# Adafruit_NeoPixel_Ring_16.net
KiCad netlist of a schematic drawn in EAGLE
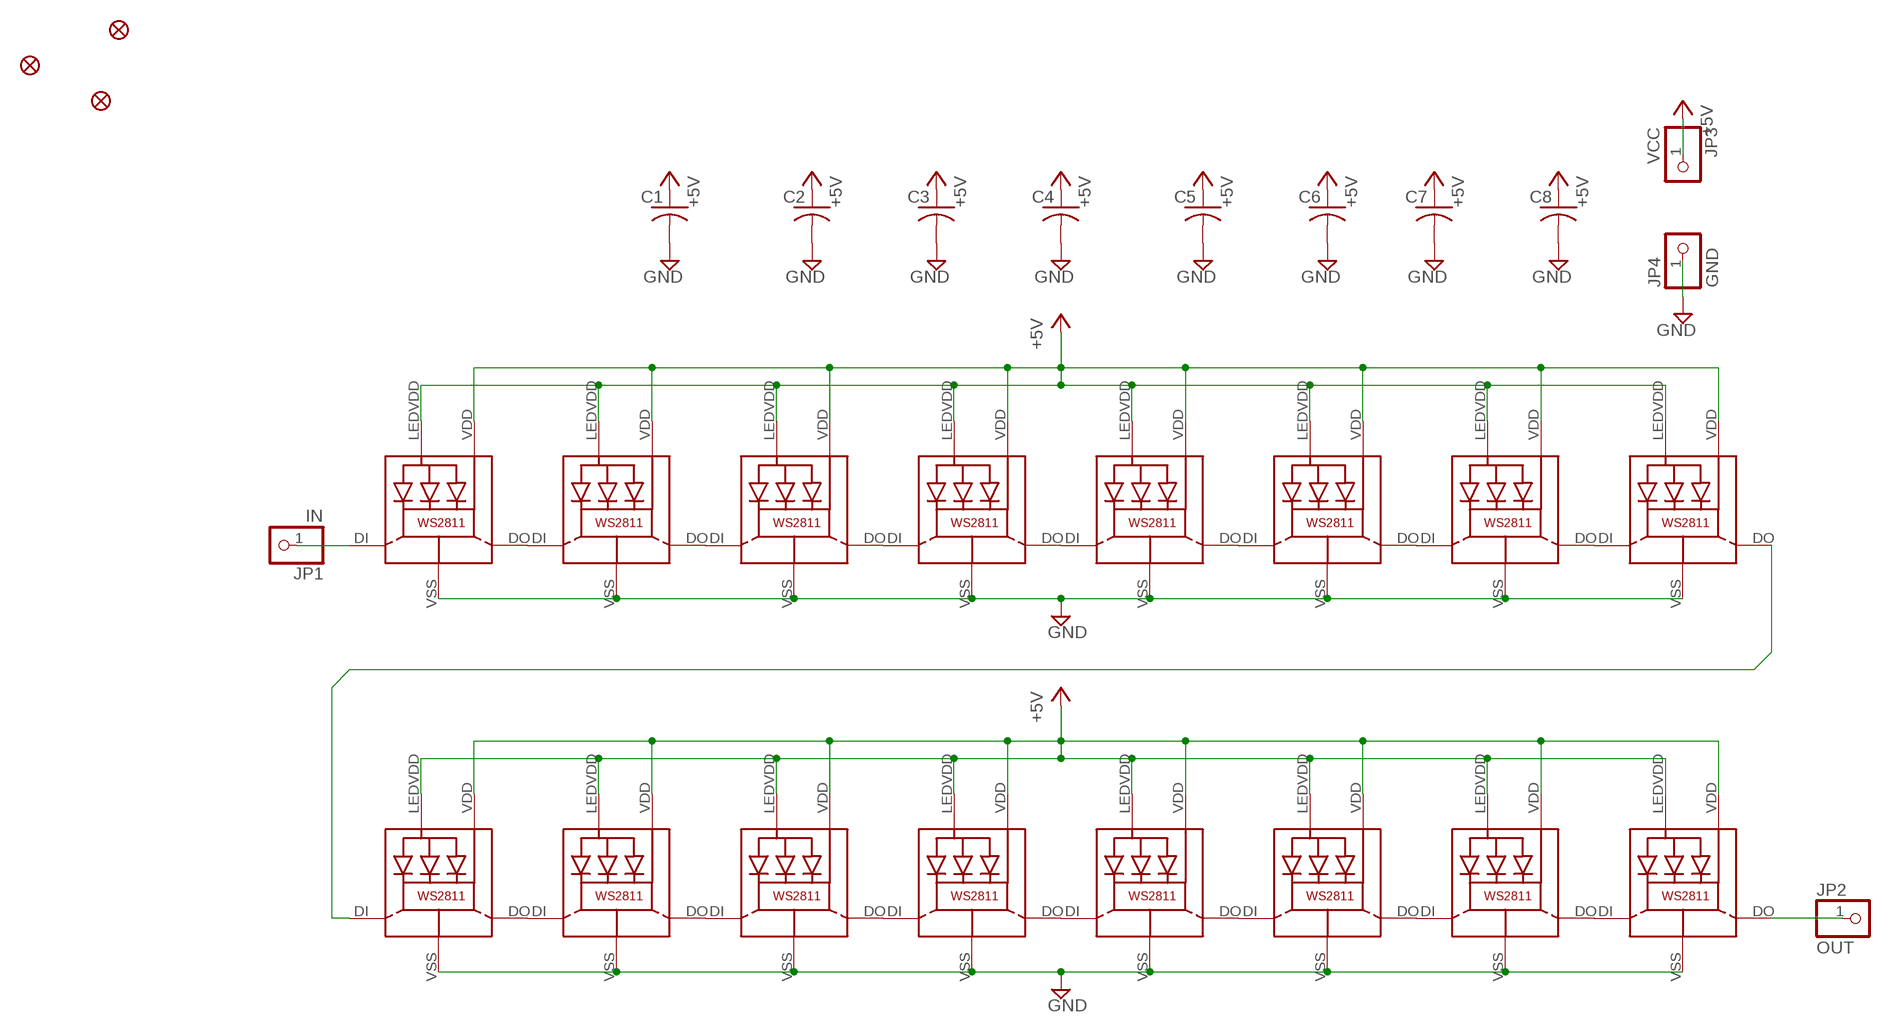
[diagram p0: schematic, sheet 1]

(export (version "E")
  (design (tool "Eeschema 10.0.6"))
  (components
    (comp (ref "C1")
      (value "C-USC0603")
      (footprint "eagle-import:C0603")
      (libsource (lib "eagle-import") (part "C-USC0603"))
    )
    (comp (ref "C2")
      (value "C-USC0603K")
      (footprint "eagle-import:C0603K")
      (libsource (lib "eagle-import") (part "C-USC0603K"))
    )
    (comp (ref "C3")
      (value "C-USC0603K")
      (footprint "eagle-import:C0603K")
      (libsource (lib "eagle-import") (part "C-USC0603K"))
    )
    (comp (ref "C4")
      (value "C-USC0603K")
      (footprint "eagle-import:C0603K")
      (libsource (lib "eagle-import") (part "C-USC0603K"))
    )
    (comp (ref "C5")
      (value "C-USC0603K")
      (footprint "eagle-import:C0603K")
      (libsource (lib "eagle-import") (part "C-USC0603K"))
    )
    (comp (ref "C6")
      (value "C-USC0603K")
      (footprint "eagle-import:C0603K")
      (libsource (lib "eagle-import") (part "C-USC0603K"))
    )
    (comp (ref "C7")
      (value "C-USC0603K")
      (footprint "eagle-import:C0603K")
      (libsource (lib "eagle-import") (part "C-USC0603K"))
    )
    (comp (ref "C8")
      (value "C-USC0603K")
      (footprint "eagle-import:C0603K")
      (libsource (lib "eagle-import") (part "C-USC0603K"))
    )
    (comp (ref "FID1")
      (value "FIDUCIAL\"\"")
      (footprint "eagle-import:FIDUCIAL_1MM")
      (libsource (lib "eagle-import") (part "FIDUCIAL{dblquote}{dblquote}"))
    )
    (comp (ref "FID2")
      (value "FIDUCIAL\"\"")
      (footprint "eagle-import:FIDUCIAL_1MM")
      (libsource (lib "eagle-import") (part "FIDUCIAL{dblquote}{dblquote}"))
    )
    (comp (ref "FID3")
      (value "FIDUCIAL\"\"")
      (footprint "eagle-import:FIDUCIAL_1MM")
      (libsource (lib "eagle-import") (part "FIDUCIAL{dblquote}{dblquote}"))
    )
    (comp (ref "JP1")
      (value "IN")
      (footprint "eagle-import:1X01-CLEANBIG")
      (libsource (lib "eagle-import") (part "PINHD-1X1CB"))
    )
    (comp (ref "JP2")
      (value "OUT")
      (footprint "eagle-import:1X01-CLEANBIG")
      (libsource (lib "eagle-import") (part "PINHD-1X1CB"))
    )
    (comp (ref "JP3")
      (value "VCC")
      (footprint "eagle-import:1X01-CLEANBIG")
      (libsource (lib "eagle-import") (part "PINHD-1X1CB"))
    )
    (comp (ref "JP4")
      (value "GND")
      (footprint "eagle-import:1X01-CLEANBIG")
      (libsource (lib "eagle-import") (part "PINHD-1X1CB"))
    )
    (comp (ref "LED1")
      (value "WS28115050")
      (footprint "eagle-import:WS28115050")
      (libsource (lib "eagle-import") (part "WS28115050"))
    )
    (comp (ref "LED2")
      (value "WS28115050")
      (footprint "eagle-import:WS28115050")
      (libsource (lib "eagle-import") (part "WS28115050"))
    )
    (comp (ref "LED3")
      (value "WS28115050")
      (footprint "eagle-import:WS28115050")
      (libsource (lib "eagle-import") (part "WS28115050"))
    )
    (comp (ref "LED4")
      (value "WS28115050")
      (footprint "eagle-import:WS28115050")
      (libsource (lib "eagle-import") (part "WS28115050"))
    )
    (comp (ref "LED5")
      (value "WS28115050")
      (footprint "eagle-import:WS28115050")
      (libsource (lib "eagle-import") (part "WS28115050"))
    )
    (comp (ref "LED6")
      (value "WS28115050")
      (footprint "eagle-import:WS28115050")
      (libsource (lib "eagle-import") (part "WS28115050"))
    )
    (comp (ref "LED7")
      (value "WS28115050")
      (footprint "eagle-import:WS28115050")
      (libsource (lib "eagle-import") (part "WS28115050"))
    )
    (comp (ref "LED8")
      (value "WS28115050")
      (footprint "eagle-import:WS28115050")
      (libsource (lib "eagle-import") (part "WS28115050"))
    )
    (comp (ref "LED9")
      (value "WS28115050")
      (footprint "eagle-import:WS28115050")
      (libsource (lib "eagle-import") (part "WS28115050"))
    )
    (comp (ref "LED10")
      (value "WS28115050")
      (footprint "eagle-import:WS28115050")
      (libsource (lib "eagle-import") (part "WS28115050"))
    )
    (comp (ref "LED11")
      (value "WS28115050")
      (footprint "eagle-import:WS28115050")
      (libsource (lib "eagle-import") (part "WS28115050"))
    )
    (comp (ref "LED12")
      (value "WS28115050")
      (footprint "eagle-import:WS28115050")
      (libsource (lib "eagle-import") (part "WS28115050"))
    )
    (comp (ref "LED13")
      (value "WS28115050")
      (footprint "eagle-import:WS28115050")
      (libsource (lib "eagle-import") (part "WS28115050"))
    )
    (comp (ref "LED14")
      (value "WS28115050")
      (footprint "eagle-import:WS28115050")
      (libsource (lib "eagle-import") (part "WS28115050"))
    )
    (comp (ref "LED15")
      (value "WS28115050")
      (footprint "eagle-import:WS28115050")
      (libsource (lib "eagle-import") (part "WS28115050"))
    )
    (comp (ref "LED16")
      (value "WS28115050")
      (footprint "eagle-import:WS28115050")
      (libsource (lib "eagle-import") (part "WS28115050"))
    )
  )
  (nets
    (net (code "1") (name "+5V") (class "Default")
      (node (ref "C1") (pin "1") (pinfunction "1_1") (pintype "passive"))
      (node (ref "C2") (pin "1") (pinfunction "1_1") (pintype "passive"))
      (node (ref "C3") (pin "1") (pinfunction "1_1") (pintype "passive"))
      (node (ref "C4") (pin "1") (pinfunction "1_1") (pintype "passive"))
      (node (ref "C5") (pin "1") (pinfunction "1_1") (pintype "passive"))
      (node (ref "C6") (pin "1") (pinfunction "1_1") (pintype "passive"))
      (node (ref "C7") (pin "1") (pinfunction "1_1") (pintype "passive"))
      (node (ref "C8") (pin "1") (pinfunction "1_1") (pintype "passive"))
      (node (ref "JP3") (pin "1") (pinfunction "1_1") (pintype "passive"))
      (node (ref "LED1") (pin "LEDVDD") (pinfunction "LEDVDD_LEDVDD") (pintype "power_in"))
      (node (ref "LED1") (pin "VDD") (pinfunction "VDD_VDD") (pintype "power_in"))
      (node (ref "LED10") (pin "LEDVDD") (pinfunction "LEDVDD_LEDVDD") (pintype "power_in"))
      (node (ref "LED10") (pin "VDD") (pinfunction "VDD_VDD") (pintype "power_in"))
      (node (ref "LED11") (pin "LEDVDD") (pinfunction "LEDVDD_LEDVDD") (pintype "power_in"))
      (node (ref "LED11") (pin "VDD") (pinfunction "VDD_VDD") (pintype "power_in"))
      (node (ref "LED12") (pin "LEDVDD") (pinfunction "LEDVDD_LEDVDD") (pintype "power_in"))
      (node (ref "LED12") (pin "VDD") (pinfunction "VDD_VDD") (pintype "power_in"))
      (node (ref "LED13") (pin "LEDVDD") (pinfunction "LEDVDD_LEDVDD") (pintype "power_in"))
      (node (ref "LED13") (pin "VDD") (pinfunction "VDD_VDD") (pintype "power_in"))
      (node (ref "LED14") (pin "LEDVDD") (pinfunction "LEDVDD_LEDVDD") (pintype "power_in"))
      (node (ref "LED14") (pin "VDD") (pinfunction "VDD_VDD") (pintype "power_in"))
      (node (ref "LED15") (pin "LEDVDD") (pinfunction "LEDVDD_LEDVDD") (pintype "power_in"))
      (node (ref "LED15") (pin "VDD") (pinfunction "VDD_VDD") (pintype "power_in"))
      (node (ref "LED16") (pin "LEDVDD") (pinfunction "LEDVDD_LEDVDD") (pintype "power_in"))
      (node (ref "LED16") (pin "VDD") (pinfunction "VDD_VDD") (pintype "power_in"))
      (node (ref "LED2") (pin "LEDVDD") (pinfunction "LEDVDD_LEDVDD") (pintype "power_in"))
      (node (ref "LED2") (pin "VDD") (pinfunction "VDD_VDD") (pintype "power_in"))
      (node (ref "LED3") (pin "LEDVDD") (pinfunction "LEDVDD_LEDVDD") (pintype "power_in"))
      (node (ref "LED3") (pin "VDD") (pinfunction "VDD_VDD") (pintype "power_in"))
      (node (ref "LED4") (pin "LEDVDD") (pinfunction "LEDVDD_LEDVDD") (pintype "power_in"))
      (node (ref "LED4") (pin "VDD") (pinfunction "VDD_VDD") (pintype "power_in"))
      (node (ref "LED5") (pin "LEDVDD") (pinfunction "LEDVDD_LEDVDD") (pintype "power_in"))
      (node (ref "LED5") (pin "VDD") (pinfunction "VDD_VDD") (pintype "power_in"))
      (node (ref "LED6") (pin "LEDVDD") (pinfunction "LEDVDD_LEDVDD") (pintype "power_in"))
      (node (ref "LED6") (pin "VDD") (pinfunction "VDD_VDD") (pintype "power_in"))
      (node (ref "LED7") (pin "LEDVDD") (pinfunction "LEDVDD_LEDVDD") (pintype "power_in"))
      (node (ref "LED7") (pin "VDD") (pinfunction "VDD_VDD") (pintype "power_in"))
      (node (ref "LED8") (pin "LEDVDD") (pinfunction "LEDVDD_LEDVDD") (pintype "power_in"))
      (node (ref "LED8") (pin "VDD") (pinfunction "VDD_VDD") (pintype "power_in"))
      (node (ref "LED9") (pin "LEDVDD") (pinfunction "LEDVDD_LEDVDD") (pintype "power_in"))
      (node (ref "LED9") (pin "VDD") (pinfunction "VDD_VDD") (pintype "power_in"))
    )
    (net (code "2") (name "GND") (class "Default")
      (node (ref "C1") (pin "2") (pinfunction "2_2") (pintype "passive"))
      (node (ref "C2") (pin "2") (pinfunction "2_2") (pintype "passive"))
      (node (ref "C3") (pin "2") (pinfunction "2_2") (pintype "passive"))
      (node (ref "C4") (pin "2") (pinfunction "2_2") (pintype "passive"))
      (node (ref "C5") (pin "2") (pinfunction "2_2") (pintype "passive"))
      (node (ref "C6") (pin "2") (pinfunction "2_2") (pintype "passive"))
      (node (ref "C7") (pin "2") (pinfunction "2_2") (pintype "passive"))
      (node (ref "C8") (pin "2") (pinfunction "2_2") (pintype "passive"))
      (node (ref "JP4") (pin "1") (pinfunction "1_1") (pintype "passive"))
      (node (ref "LED1") (pin "VSS") (pinfunction "GND_VSS") (pintype "power_in"))
      (node (ref "LED10") (pin "VSS") (pinfunction "GND_VSS") (pintype "power_in"))
      (node (ref "LED11") (pin "VSS") (pinfunction "GND_VSS") (pintype "power_in"))
      (node (ref "LED12") (pin "VSS") (pinfunction "GND_VSS") (pintype "power_in"))
      (node (ref "LED13") (pin "VSS") (pinfunction "GND_VSS") (pintype "power_in"))
      (node (ref "LED14") (pin "VSS") (pinfunction "GND_VSS") (pintype "power_in"))
      (node (ref "LED15") (pin "VSS") (pinfunction "GND_VSS") (pintype "power_in"))
      (node (ref "LED16") (pin "VSS") (pinfunction "GND_VSS") (pintype "power_in"))
      (node (ref "LED2") (pin "VSS") (pinfunction "GND_VSS") (pintype "power_in"))
      (node (ref "LED3") (pin "VSS") (pinfunction "GND_VSS") (pintype "power_in"))
      (node (ref "LED4") (pin "VSS") (pinfunction "GND_VSS") (pintype "power_in"))
      (node (ref "LED5") (pin "VSS") (pinfunction "GND_VSS") (pintype "power_in"))
      (node (ref "LED6") (pin "VSS") (pinfunction "GND_VSS") (pintype "power_in"))
      (node (ref "LED7") (pin "VSS") (pinfunction "GND_VSS") (pintype "power_in"))
      (node (ref "LED8") (pin "VSS") (pinfunction "GND_VSS") (pintype "power_in"))
      (node (ref "LED9") (pin "VSS") (pinfunction "GND_VSS") (pintype "power_in"))
    )
    (net (code "3") (name "Net-(JP1-Pad1)") (class "Default")
      (node (ref "JP1") (pin "1") (pinfunction "1_1") (pintype "passive"))
      (node (ref "LED1") (pin "DI") (pinfunction "DI_DI") (pintype "input"))
    )
    (net (code "4") (name "Net-(JP2-Pad1)") (class "Default")
      (node (ref "JP2") (pin "1") (pinfunction "1_1") (pintype "passive"))
      (node (ref "LED16") (pin "DO") (pinfunction "DO_DO") (pintype "output"))
    )
    (net (code "5") (name "Net-(LED1-PadDO)") (class "Default")
      (node (ref "LED1") (pin "DO") (pinfunction "DO_DO") (pintype "output"))
      (node (ref "LED2") (pin "DI") (pinfunction "DI_DI") (pintype "input"))
    )
    (net (code "6") (name "Net-(LED2-PadDO)") (class "Default")
      (node (ref "LED2") (pin "DO") (pinfunction "DO_DO") (pintype "output"))
      (node (ref "LED3") (pin "DI") (pinfunction "DI_DI") (pintype "input"))
    )
    (net (code "7") (name "Net-(LED3-PadDO)") (class "Default")
      (node (ref "LED3") (pin "DO") (pinfunction "DO_DO") (pintype "output"))
      (node (ref "LED4") (pin "DI") (pinfunction "DI_DI") (pintype "input"))
    )
    (net (code "8") (name "Net-(LED4-PadDO)") (class "Default")
      (node (ref "LED4") (pin "DO") (pinfunction "DO_DO") (pintype "output"))
      (node (ref "LED5") (pin "DI") (pinfunction "DI_DI") (pintype "input"))
    )
    (net (code "9") (name "Net-(LED5-PadDO)") (class "Default")
      (node (ref "LED5") (pin "DO") (pinfunction "DO_DO") (pintype "output"))
      (node (ref "LED6") (pin "DI") (pinfunction "DI_DI") (pintype "input"))
    )
    (net (code "10") (name "Net-(LED6-PadDO)") (class "Default")
      (node (ref "LED6") (pin "DO") (pinfunction "DO_DO") (pintype "output"))
      (node (ref "LED7") (pin "DI") (pinfunction "DI_DI") (pintype "input"))
    )
    (net (code "11") (name "Net-(LED7-PadDO)") (class "Default")
      (node (ref "LED7") (pin "DO") (pinfunction "DO_DO") (pintype "output"))
      (node (ref "LED8") (pin "DI") (pinfunction "DI_DI") (pintype "input"))
    )
    (net (code "12") (name "Net-(LED8-PadDO)") (class "Default")
      (node (ref "LED8") (pin "DO") (pinfunction "DO_DO") (pintype "output"))
      (node (ref "LED9") (pin "DI") (pinfunction "DI_DI") (pintype "input"))
    )
    (net (code "13") (name "Net-(LED10-PadDI)") (class "Default")
      (node (ref "LED10") (pin "DI") (pinfunction "DI_DI") (pintype "input"))
      (node (ref "LED9") (pin "DO") (pinfunction "DO_DO") (pintype "output"))
    )
    (net (code "14") (name "Net-(LED10-PadDO)") (class "Default")
      (node (ref "LED10") (pin "DO") (pinfunction "DO_DO") (pintype "output"))
      (node (ref "LED11") (pin "DI") (pinfunction "DI_DI") (pintype "input"))
    )
    (net (code "15") (name "Net-(LED11-PadDO)") (class "Default")
      (node (ref "LED11") (pin "DO") (pinfunction "DO_DO") (pintype "output"))
      (node (ref "LED12") (pin "DI") (pinfunction "DI_DI") (pintype "input"))
    )
    (net (code "16") (name "Net-(LED12-PadDO)") (class "Default")
      (node (ref "LED12") (pin "DO") (pinfunction "DO_DO") (pintype "output"))
      (node (ref "LED13") (pin "DI") (pinfunction "DI_DI") (pintype "input"))
    )
    (net (code "17") (name "Net-(LED13-PadDO)") (class "Default")
      (node (ref "LED13") (pin "DO") (pinfunction "DO_DO") (pintype "output"))
      (node (ref "LED14") (pin "DI") (pinfunction "DI_DI") (pintype "input"))
    )
    (net (code "18") (name "Net-(LED14-PadDO)") (class "Default")
      (node (ref "LED14") (pin "DO") (pinfunction "DO_DO") (pintype "output"))
      (node (ref "LED15") (pin "DI") (pinfunction "DI_DI") (pintype "input"))
    )
    (net (code "19") (name "Net-(LED15-PadDO)") (class "Default")
      (node (ref "LED15") (pin "DO") (pinfunction "DO_DO") (pintype "output"))
      (node (ref "LED16") (pin "DI") (pinfunction "DI_DI") (pintype "input"))
    )
  )
)
